# Komorebi_kit.net
KiCad netlist of a schematic drawn in EAGLE
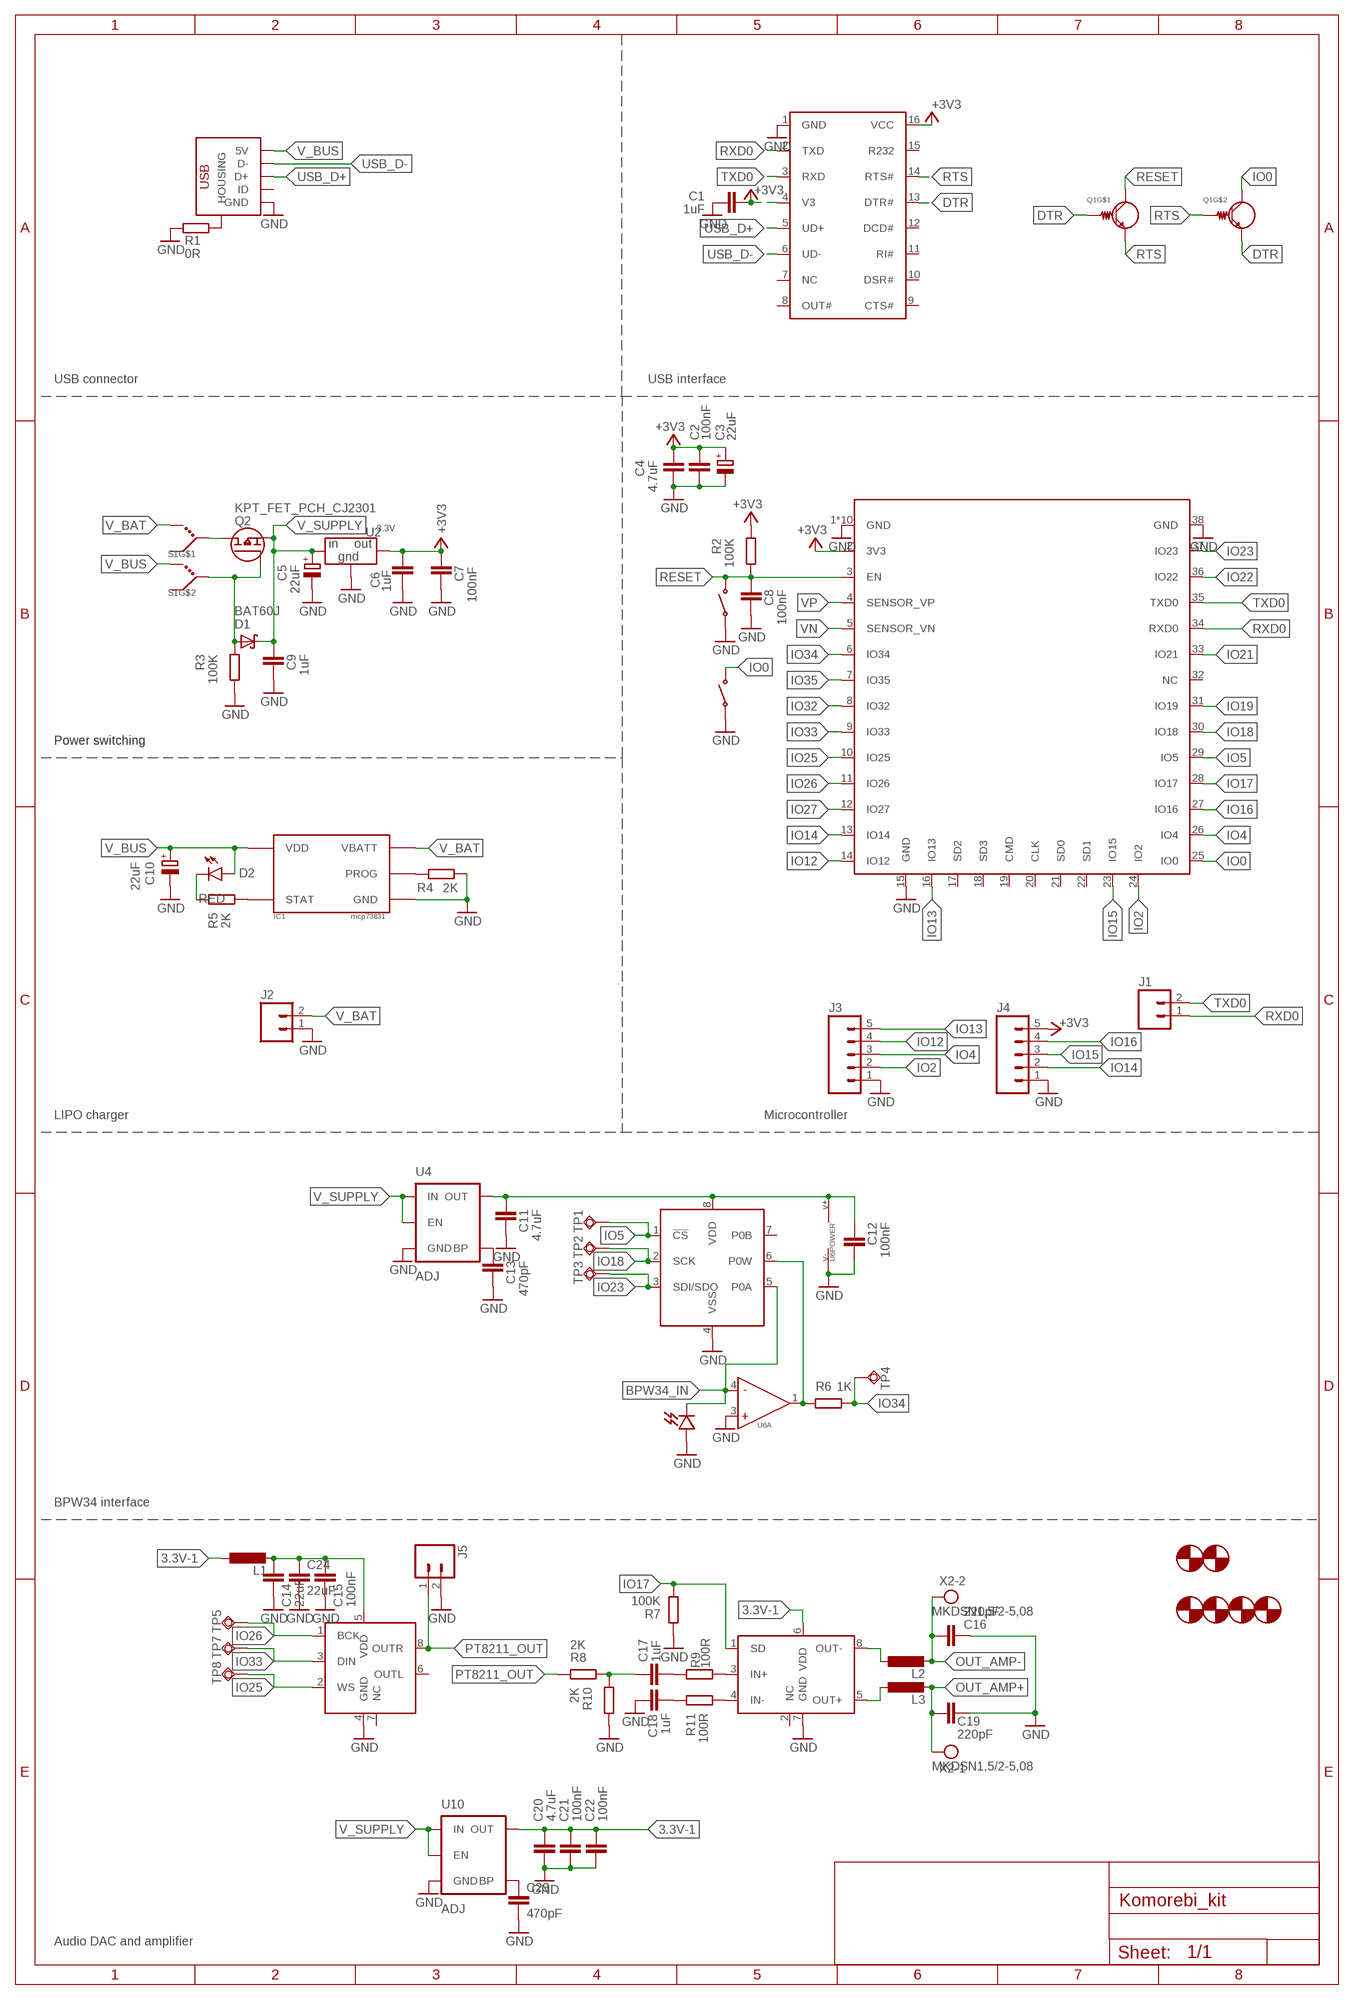
[diagram p0: schematic, sheet 1]

(export (version "E")
  (design (tool "Eeschema 10.0.6"))
  (components
    (comp (ref "C1")
      (value "1uF")
      (footprint "eagle-import:C0603")
      (libsource (lib "eagle-import") (part "C-EUC0603"))
    )
    (comp (ref "C2")
      (value "100nF")
      (footprint "eagle-import:C0603")
      (libsource (lib "eagle-import") (part "C-EUC0603"))
    )
    (comp (ref "C3")
      (value "22uF")
      (footprint "eagle-import:PANASONIC_B")
      (libsource (lib "eagle-import") (part "CPOL-EUB"))
    )
    (comp (ref "C4")
      (value "4.7uF")
      (footprint "eagle-import:C0603")
      (libsource (lib "eagle-import") (part "C-EUC0603"))
    )
    (comp (ref "C5")
      (value "22uF")
      (footprint "eagle-import:PANASONIC_B")
      (libsource (lib "eagle-import") (part "CPOL-EUB"))
    )
    (comp (ref "C6")
      (value "1uF")
      (footprint "eagle-import:C0603")
      (libsource (lib "eagle-import") (part "C-EUC0603"))
    )
    (comp (ref "C7")
      (value "100nF")
      (footprint "eagle-import:C0603")
      (libsource (lib "eagle-import") (part "C-EUC0603"))
    )
    (comp (ref "C8")
      (value "100nF")
      (footprint "eagle-import:C0603")
      (libsource (lib "eagle-import") (part "C-EUC0603"))
    )
    (comp (ref "C9")
      (value "1uF")
      (footprint "eagle-import:C0603")
      (libsource (lib "eagle-import") (part "C-EUC0603"))
    )
    (comp (ref "C10")
      (value "22uF")
      (footprint "eagle-import:PANASONIC_B")
      (libsource (lib "eagle-import") (part "CPOL-EUB"))
    )
    (comp (ref "C11")
      (value "4.7uF")
      (footprint "eagle-import:C0603")
      (libsource (lib "eagle-import") (part "C-EUC0603"))
    )
    (comp (ref "C12")
      (value "100nF")
      (footprint "eagle-import:C0603")
      (libsource (lib "eagle-import") (part "C-EUC0603"))
    )
    (comp (ref "C13")
      (value "470pF")
      (footprint "eagle-import:C0603")
      (libsource (lib "eagle-import") (part "C-EUC0603"))
    )
    (comp (ref "C14")
      (value "22uF")
      (footprint "eagle-import:C0805")
      (libsource (lib "eagle-import") (part "C-EUC0805"))
    )
    (comp (ref "C15")
      (value "100nF")
      (footprint "eagle-import:C0603")
      (libsource (lib "eagle-import") (part "C-EUC0603"))
    )
    (comp (ref "C16")
      (value "220pF")
      (footprint "eagle-import:C0603")
      (libsource (lib "eagle-import") (part "C-EUC0603"))
    )
    (comp (ref "C17")
      (value "1uF")
      (footprint "eagle-import:C0603")
      (libsource (lib "eagle-import") (part "C-EUC0603"))
    )
    (comp (ref "C18")
      (value "1uF")
      (footprint "eagle-import:C0603")
      (libsource (lib "eagle-import") (part "C-EUC0603"))
    )
    (comp (ref "C19")
      (value "220pF")
      (footprint "eagle-import:C0603")
      (libsource (lib "eagle-import") (part "C-EUC0603"))
    )
    (comp (ref "C20")
      (value "4.7uF")
      (footprint "eagle-import:C0603")
      (libsource (lib "eagle-import") (part "C-EUC0603"))
    )
    (comp (ref "C21")
      (value "100nF")
      (footprint "eagle-import:C0603")
      (libsource (lib "eagle-import") (part "C-EUC0603"))
    )
    (comp (ref "C22")
      (value "100nF")
      (footprint "eagle-import:C0603")
      (libsource (lib "eagle-import") (part "C-EUC0603"))
    )
    (comp (ref "C23")
      (value "470pF")
      (footprint "eagle-import:C0603")
      (libsource (lib "eagle-import") (part "C-EUC0603"))
    )
    (comp (ref "C24")
      (value "22uF")
      (footprint "eagle-import:C0805")
      (libsource (lib "eagle-import") (part "C-EUC0805"))
    )
    (comp (ref "D1")
      (value "BAT60J")
      (footprint "eagle-import:SOD323_ST")
      (libsource (lib "eagle-import") (part "BAT60J"))
    )
    (comp (ref "D2")
      (value "RED")
      (footprint "eagle-import:LED-1206")
      (libsource (lib "eagle-import") (part "LED1206"))
    )
    (comp (ref "D3")
      (value "KPT_SENSORS_BPW34")
      (footprint "eagle-import:BPW34")
      (libsource (lib "eagle-import") (part "KPT_SENSORS_BPW34"))
    )
    (comp (ref "H1")
      (value "KPT_HOLE3.0")
      (footprint "eagle-import:3.0MOUNTHOLE")
      (libsource (lib "eagle-import") (part "KPT_HOLE3.0"))
    )
    (comp (ref "H2")
      (value "KPT_HOLE3.0")
      (footprint "eagle-import:3.0MOUNTHOLE")
      (libsource (lib "eagle-import") (part "KPT_HOLE3.0"))
    )
    (comp (ref "H3")
      (value "KPT_HOLE4.1")
      (footprint "eagle-import:4.1MOUNTHOLE")
      (libsource (lib "eagle-import") (part "KPT_HOLE4.1"))
    )
    (comp (ref "H4")
      (value "KPT_HOLE4.1")
      (footprint "eagle-import:4.1MOUNTHOLE")
      (libsource (lib "eagle-import") (part "KPT_HOLE4.1"))
    )
    (comp (ref "H5")
      (value "KPT_HOLE4.1")
      (footprint "eagle-import:4.1MOUNTHOLE")
      (libsource (lib "eagle-import") (part "KPT_HOLE4.1"))
    )
    (comp (ref "H6")
      (value "KPT_HOLE4.1")
      (footprint "eagle-import:4.1MOUNTHOLE")
      (libsource (lib "eagle-import") (part "KPT_HOLE4.1"))
    )
    (comp (ref "IC1")
      (value "KPT_CHARGER_MCP73831")
      (footprint "eagle-import:SOT23-5")
      (libsource (lib "eagle-import") (part "KPT_CHARGER_MCP73831"))
    )
    (comp (ref "J1")
      (value "M02PTH")
      (footprint "eagle-import:1X02")
      (libsource (lib "eagle-import") (part "M02PTH"))
    )
    (comp (ref "J2")
      (value "M02PTH")
      (footprint "eagle-import:1X02")
      (libsource (lib "eagle-import") (part "M02PTH"))
    )
    (comp (ref "J3")
      (value "M05PTH")
      (footprint "eagle-import:1X05")
      (libsource (lib "eagle-import") (part "M05PTH"))
    )
    (comp (ref "J4")
      (value "M05PTH")
      (footprint "eagle-import:1X05")
      (libsource (lib "eagle-import") (part "M05PTH"))
    )
    (comp (ref "J5")
      (value "M02PTH")
      (footprint "eagle-import:1X02")
      (libsource (lib "eagle-import") (part "M02PTH"))
    )
    (comp (ref "L1")
      (value "L-EUL2012C")
      (footprint "eagle-import:L2012C")
      (libsource (lib "eagle-import") (part "L-EUL2012C"))
    )
    (comp (ref "L2")
      (value "L-EUL2012C")
      (footprint "eagle-import:L2012C")
      (libsource (lib "eagle-import") (part "L-EUL2012C"))
    )
    (comp (ref "L3")
      (value "L-EUL2012C")
      (footprint "eagle-import:L2012C")
      (libsource (lib "eagle-import") (part "L-EUL2012C"))
    )
    (comp (ref "Q1")
      (value "KPT_UMH3N")
      (footprint "eagle-import:SOT363")
      (libsource (lib "eagle-import") (part "KPT_UMH3N"))
    )
    (comp (ref "Q2")
      (value "KPT_FET_PCH_CJ2301")
      (footprint "eagle-import:SOT23")
      (libsource (lib "eagle-import") (part "KPT_FET_PCH_CJ2301"))
    )
    (comp (ref "R1")
      (value "0R")
      (footprint "eagle-import:R0603")
      (libsource (lib "eagle-import") (part "R-EU_R0603"))
    )
    (comp (ref "R2")
      (value "100K")
      (footprint "eagle-import:R0603")
      (libsource (lib "eagle-import") (part "R-EU_R0603"))
    )
    (comp (ref "R3")
      (value "100K")
      (footprint "eagle-import:R0603")
      (libsource (lib "eagle-import") (part "R-EU_R0603"))
    )
    (comp (ref "R4")
      (value "2K")
      (footprint "eagle-import:R0603")
      (libsource (lib "eagle-import") (part "R-EU_R0603"))
    )
    (comp (ref "R5")
      (value "2K")
      (footprint "eagle-import:R0603")
      (libsource (lib "eagle-import") (part "R-EU_R0603"))
    )
    (comp (ref "R6")
      (value "1K")
      (footprint "eagle-import:R0603")
      (libsource (lib "eagle-import") (part "R-EU_R0603"))
    )
    (comp (ref "R7")
      (value "100K")
      (footprint "eagle-import:R0603")
      (libsource (lib "eagle-import") (part "R-EU_R0603"))
    )
    (comp (ref "R8")
      (value "2K")
      (footprint "eagle-import:R0603")
      (libsource (lib "eagle-import") (part "R-EU_R0603"))
    )
    (comp (ref "R9")
      (value "100R")
      (footprint "eagle-import:R0603")
      (libsource (lib "eagle-import") (part "R-EU_R0603"))
    )
    (comp (ref "R10")
      (value "2K")
      (footprint "eagle-import:R0603")
      (libsource (lib "eagle-import") (part "R-EU_R0603"))
    )
    (comp (ref "R11")
      (value "100R")
      (footprint "eagle-import:R0603")
      (libsource (lib "eagle-import") (part "R-EU_R0603"))
    )
    (comp (ref "S1")
      (value "KPT_SWITCH_JS202011AQN")
      (footprint "eagle-import:C&K_JS202011AQN")
      (libsource (lib "eagle-import") (part "KPT_SWITCH_JS202011AQN"))
    )
    (comp (ref "S2")
      (value "TACT_SWITCH_C318884")
      (footprint "eagle-import:SWITCH_TACTILE_C318884")
      (libsource (lib "eagle-import") (part "TACT_SWITCH_C318884"))
    )
    (comp (ref "S3")
      (value "TACT_SWITCH_C318884")
      (footprint "eagle-import:SWITCH_TACTILE_C318884")
      (libsource (lib "eagle-import") (part "TACT_SWITCH_C318884"))
    )
    (comp (ref "TP1")
      (value "TPSQB1,27")
      (footprint "eagle-import:B1,27")
      (libsource (lib "eagle-import") (part "TPSQB1,27"))
    )
    (comp (ref "TP2")
      (value "TPSQB1,27")
      (footprint "eagle-import:B1,27")
      (libsource (lib "eagle-import") (part "TPSQB1,27"))
    )
    (comp (ref "TP3")
      (value "TPSQB1,27")
      (footprint "eagle-import:B1,27")
      (libsource (lib "eagle-import") (part "TPSQB1,27"))
    )
    (comp (ref "TP4")
      (value "TPSQB1,27")
      (footprint "eagle-import:B1,27")
      (libsource (lib "eagle-import") (part "TPSQB1,27"))
    )
    (comp (ref "TP5")
      (value "TPSQB1,27")
      (footprint "eagle-import:B1,27")
      (libsource (lib "eagle-import") (part "TPSQB1,27"))
    )
    (comp (ref "TP7")
      (value "TPSQB1,27")
      (footprint "eagle-import:B1,27")
      (libsource (lib "eagle-import") (part "TPSQB1,27"))
    )
    (comp (ref "TP8")
      (value "TPSQB1,27")
      (footprint "eagle-import:B1,27")
      (libsource (lib "eagle-import") (part "TPSQB1,27"))
    )
    (comp (ref "U1")
      (value "KPT_CH340C")
      (footprint "eagle-import:SOIC16")
      (libsource (lib "eagle-import") (part "KPT_CH340C"))
    )
    (comp (ref "U2")
      (value "3.3V")
      (footprint "eagle-import:SOT-89-3L")
      (libsource (lib "eagle-import") (part "KPT_VREG_APT7215"))
    )
    (comp (ref "U3")
      (value "KPT_ESP32")
      (footprint "eagle-import:WROOM_ESP32")
      (libsource (lib "eagle-import") (part "KPT_ESP32"))
    )
    (comp (ref "U4")
      (value "ADJ")
      (footprint "eagle-import:SOT23-5")
      (libsource (lib "eagle-import") (part "V_REG_MIC5205ADJ"))
    )
    (comp (ref "U5")
      (value "KPT_DIGIPOT_MCP41X1SOIC8")
      (footprint "eagle-import:SOIC-8")
      (libsource (lib "eagle-import") (part "KPT_DIGIPOT_MCP41X1SOIC8"))
    )
    (comp (ref "U6")
      (value "KPT_OPAMP_MCP6001")
      (footprint "eagle-import:SOT23-5")
      (libsource (lib "eagle-import") (part "KPT_OPAMP_MCP6001"))
    )
    (comp (ref "U7")
      (value "KPT_DAC_PT8211")
      (footprint "eagle-import:SOIC-8")
      (libsource (lib "eagle-import") (part "KPT_DAC_PT8211"))
    )
    (comp (ref "U8")
      (value "KPT_AMP-D_PAM8302SOIC8")
      (footprint "eagle-import:SOIC-8")
      (libsource (lib "eagle-import") (part "KPT_AMP-D_PAM8302SOIC8"))
    )
    (comp (ref "U10")
      (value "ADJ")
      (footprint "eagle-import:SOT23-5")
      (libsource (lib "eagle-import") (part "V_REG_MIC5205ADJ"))
    )
    (comp (ref "X1")
      (value "USB_MICROB_C10418")
      (footprint "eagle-import:USB_MICROB_C10418")
      (libsource (lib "eagle-import") (part "USB_MICROB_C10418"))
    )
    (comp (ref "X2")
      (value "MKDSN1,5/2-5,08")
      (footprint "eagle-import:MKDSN1,5_2-5,08")
      (libsource (lib "eagle-import") (part "MKDSN1,5/2-5,08"))
    )
  )
  (nets
    (net (code "1") (name "+3V3") (class "Default")
      (node (ref "C1") (pin "2") (pinfunction "2_2") (pintype "passive"))
      (node (ref "C2") (pin "1") (pinfunction "1_1") (pintype "passive"))
      (node (ref "C3") (pin "+") (pinfunction "+_+") (pintype "passive"))
      (node (ref "C4") (pin "2") (pinfunction "2_2") (pintype "passive"))
      (node (ref "C6") (pin "1") (pinfunction "1_1") (pintype "passive"))
      (node (ref "C7") (pin "1") (pinfunction "1_1") (pintype "passive"))
      (node (ref "J4") (pin "5") (pinfunction "5_5") (pintype "passive"))
      (node (ref "R2") (pin "2") (pinfunction "2_2") (pintype "passive"))
      (node (ref "U1") (pin "16") (pinfunction "VCC_16") (pintype "bidirectional"))
      (node (ref "U1") (pin "4") (pinfunction "V3_4") (pintype "bidirectional"))
      (node (ref "U2") (pin "P$3") (pinfunction "OUT_P$3") (pintype "bidirectional"))
      (node (ref "U3") (pin "2") (pinfunction "3V3_2") (pintype "bidirectional"))
    )
    (net (code "2") (name "3.3V-1") (class "Default")
      (node (ref "C20") (pin "1") (pinfunction "1_1") (pintype "passive"))
      (node (ref "C21") (pin "1") (pinfunction "1_1") (pintype "passive"))
      (node (ref "C22") (pin "1") (pinfunction "1_1") (pintype "passive"))
      (node (ref "L1") (pin "1") (pinfunction "1_1") (pintype "passive"))
      (node (ref "U10") (pin "5") (pinfunction "OUT_5") (pintype "passive"))
      (node (ref "U8") (pin "6") (pinfunction "VDD_6") (pintype "bidirectional"))
    )
    (net (code "3") (name "BPW34_IN") (class "Default")
      (node (ref "D3") (pin "CATHODE") (pinfunction "CATHODE_CATHODE") (pintype "bidirectional"))
      (node (ref "U5") (pin "5") (pinfunction "P0A_5") (pintype "bidirectional"))
      (node (ref "U6") (pin "4") (pinfunction "-_4") (pintype "bidirectional"))
    )
    (net (code "4") (name "DTR") (class "Default")
      (node (ref "Q1") (pin "2") (pinfunction "BASE_2") (pintype "bidirectional"))
      (node (ref "Q1") (pin "4") (pinfunction "EMITTER_4") (pintype "bidirectional"))
      (node (ref "U1") (pin "13") (pinfunction "DTR#_13") (pintype "bidirectional"))
    )
    (net (code "5") (name "GND") (class "Default")
      (node (ref "C1") (pin "1") (pinfunction "1_1") (pintype "passive"))
      (node (ref "C10") (pin "-") (pinfunction "-_-") (pintype "passive"))
      (node (ref "C11") (pin "2") (pinfunction "2_2") (pintype "passive"))
      (node (ref "C12") (pin "2") (pinfunction "2_2") (pintype "passive"))
      (node (ref "C13") (pin "2") (pinfunction "2_2") (pintype "passive"))
      (node (ref "C14") (pin "2") (pinfunction "2_2") (pintype "passive"))
      (node (ref "C15") (pin "2") (pinfunction "2_2") (pintype "passive"))
      (node (ref "C16") (pin "1") (pinfunction "1_1") (pintype "passive"))
      (node (ref "C18") (pin "1") (pinfunction "1_1") (pintype "passive"))
      (node (ref "C19") (pin "1") (pinfunction "1_1") (pintype "passive"))
      (node (ref "C2") (pin "2") (pinfunction "2_2") (pintype "passive"))
      (node (ref "C20") (pin "2") (pinfunction "2_2") (pintype "passive"))
      (node (ref "C21") (pin "2") (pinfunction "2_2") (pintype "passive"))
      (node (ref "C22") (pin "2") (pinfunction "2_2") (pintype "passive"))
      (node (ref "C23") (pin "2") (pinfunction "2_2") (pintype "passive"))
      (node (ref "C24") (pin "2") (pinfunction "2_2") (pintype "passive"))
      (node (ref "C3") (pin "-") (pinfunction "-_-") (pintype "passive"))
      (node (ref "C4") (pin "1") (pinfunction "1_1") (pintype "passive"))
      (node (ref "C5") (pin "-") (pinfunction "-_-") (pintype "passive"))
      (node (ref "C6") (pin "2") (pinfunction "2_2") (pintype "passive"))
      (node (ref "C7") (pin "2") (pinfunction "2_2") (pintype "passive"))
      (node (ref "C8") (pin "2") (pinfunction "2_2") (pintype "passive"))
      (node (ref "C9") (pin "2") (pinfunction "2_2") (pintype "passive"))
      (node (ref "D3") (pin "ANODE") (pinfunction "ANODE_ANODE") (pintype "bidirectional"))
      (node (ref "IC1") (pin "2") (pinfunction "GND_2") (pintype "bidirectional"))
      (node (ref "J2") (pin "1") (pinfunction "1_1") (pintype "passive"))
      (node (ref "J3") (pin "1") (pinfunction "1_1") (pintype "passive"))
      (node (ref "J4") (pin "1") (pinfunction "1_1") (pintype "passive"))
      (node (ref "J5") (pin "2") (pinfunction "2_2") (pintype "passive"))
      (node (ref "R1") (pin "1") (pinfunction "1_1") (pintype "passive"))
      (node (ref "R10") (pin "1") (pinfunction "1_1") (pintype "passive"))
      (node (ref "R3") (pin "1") (pinfunction "1_1") (pintype "passive"))
      (node (ref "R4") (pin "2") (pinfunction "2_2") (pintype "passive"))
      (node (ref "R7") (pin "1") (pinfunction "1_1") (pintype "passive"))
      (node (ref "S2") (pin "A") (pinfunction "P$1_A") (pintype "bidirectional"))
      (node (ref "S2") (pin "B") (pinfunction "P$1_B") (pintype "bidirectional"))
      (node (ref "S3") (pin "A") (pinfunction "P$1_A") (pintype "bidirectional"))
      (node (ref "S3") (pin "B") (pinfunction "P$1_B") (pintype "bidirectional"))
      (node (ref "U1") (pin "1") (pinfunction "GND_1") (pintype "bidirectional"))
      (node (ref "U10") (pin "2") (pinfunction "GND_2") (pintype "input"))
      (node (ref "U2") (pin "P$1") (pinfunction "GND_P$1") (pintype "bidirectional"))
      (node (ref "U3") (pin "1") (pinfunction "GND_1") (pintype "bidirectional"))
      (node (ref "U3") (pin "15") (pinfunction "GND_15") (pintype "bidirectional"))
      (node (ref "U3") (pin "38") (pinfunction "GND_38") (pintype "bidirectional"))
      (node (ref "U3") (pin "BP1") (pinfunction "GND_BP1") (pintype "bidirectional"))
      (node (ref "U3") (pin "BP2") (pinfunction "GND_BP2") (pintype "bidirectional"))
      (node (ref "U3") (pin "BP3") (pinfunction "GND_BP3") (pintype "bidirectional"))
      (node (ref "U3") (pin "BP4") (pinfunction "GND_BP4") (pintype "bidirectional"))
      (node (ref "U3") (pin "BP5") (pinfunction "GND_BP5") (pintype "bidirectional"))
      (node (ref "U3") (pin "BP6") (pinfunction "GND_BP6") (pintype "bidirectional"))
      (node (ref "U3") (pin "BP7") (pinfunction "GND_BP7") (pintype "bidirectional"))
      (node (ref "U3") (pin "BP8") (pinfunction "GND_BP8") (pintype "bidirectional"))
      (node (ref "U3") (pin "BP9") (pinfunction "GND_BP9") (pintype "bidirectional"))
      (node (ref "U4") (pin "2") (pinfunction "GND_2") (pintype "input"))
      (node (ref "U5") (pin "4") (pinfunction "VSS_4") (pintype "bidirectional"))
      (node (ref "U6") (pin "2") (pinfunction "V-_2") (pintype "bidirectional"))
      (node (ref "U6") (pin "3") (pinfunction "+_3") (pintype "bidirectional"))
      (node (ref "U7") (pin "4") (pinfunction "GND_4") (pintype "bidirectional"))
      (node (ref "U8") (pin "7") (pinfunction "GND_7") (pintype "bidirectional"))
      (node (ref "X1") (pin "P$1") (pinfunction "GND_P$1") (pintype "bidirectional"))
    )
    (net (code "6") (name "IO0") (class "Default")
      (node (ref "Q1") (pin "3") (pinfunction "COLLECTOR_3") (pintype "bidirectional"))
      (node (ref "S3") (pin "C") (pinfunction "P$2_C") (pintype "bidirectional"))
      (node (ref "S3") (pin "D") (pinfunction "P$2_D") (pintype "bidirectional"))
      (node (ref "U3") (pin "25") (pinfunction "IO0_25") (pintype "bidirectional"))
    )
    (net (code "7") (name "IO2") (class "Default")
      (node (ref "J3") (pin "2") (pinfunction "2_2") (pintype "passive"))
      (node (ref "U3") (pin "24") (pinfunction "IO2_24") (pintype "bidirectional"))
    )
    (net (code "8") (name "IO4") (class "Default")
      (node (ref "J3") (pin "3") (pinfunction "3_3") (pintype "passive"))
      (node (ref "U3") (pin "26") (pinfunction "IO4_26") (pintype "bidirectional"))
    )
    (net (code "9") (name "IO5") (class "Default")
      (node (ref "TP1") (pin "TP") (pinfunction "TP_TP") (pintype "input"))
      (node (ref "U3") (pin "29") (pinfunction "IO5_29") (pintype "bidirectional"))
      (node (ref "U5") (pin "1") (pinfunction "~{CS}_1") (pintype "bidirectional"))
    )
    (net (code "10") (name "IO12") (class "Default")
      (node (ref "J3") (pin "4") (pinfunction "4_4") (pintype "passive"))
      (node (ref "U3") (pin "14") (pinfunction "IO12_14") (pintype "bidirectional"))
    )
    (net (code "11") (name "IO13") (class "Default")
      (node (ref "J3") (pin "5") (pinfunction "5_5") (pintype "passive"))
      (node (ref "U3") (pin "16") (pinfunction "IO13_16") (pintype "bidirectional"))
    )
    (net (code "12") (name "IO14") (class "Default")
      (node (ref "J4") (pin "2") (pinfunction "2_2") (pintype "passive"))
      (node (ref "U3") (pin "13") (pinfunction "IO14_13") (pintype "bidirectional"))
    )
    (net (code "13") (name "IO15") (class "Default")
      (node (ref "J4") (pin "3") (pinfunction "3_3") (pintype "passive"))
      (node (ref "U3") (pin "23") (pinfunction "IO15_23") (pintype "bidirectional"))
    )
    (net (code "14") (name "IO16") (class "Default")
      (node (ref "J4") (pin "4") (pinfunction "4_4") (pintype "passive"))
      (node (ref "U3") (pin "27") (pinfunction "IO16_27") (pintype "bidirectional"))
    )
    (net (code "15") (name "IO17") (class "Default")
      (node (ref "R7") (pin "2") (pinfunction "2_2") (pintype "passive"))
      (node (ref "U3") (pin "28") (pinfunction "IO17_28") (pintype "bidirectional"))
      (node (ref "U8") (pin "1") (pinfunction "SD_1") (pintype "bidirectional"))
    )
    (net (code "16") (name "IO18") (class "Default")
      (node (ref "TP2") (pin "TP") (pinfunction "TP_TP") (pintype "input"))
      (node (ref "U3") (pin "30") (pinfunction "IO18_30") (pintype "bidirectional"))
      (node (ref "U5") (pin "2") (pinfunction "SCK_2") (pintype "bidirectional"))
    )
    (net (code "17") (name "IO19") (class "Default")
      (node (ref "U3") (pin "31") (pinfunction "IO19_31") (pintype "bidirectional"))
    )
    (net (code "18") (name "IO21") (class "Default")
      (node (ref "U3") (pin "33") (pinfunction "IO21_33") (pintype "bidirectional"))
    )
    (net (code "19") (name "IO22") (class "Default")
      (node (ref "U3") (pin "36") (pinfunction "IO22_36") (pintype "bidirectional"))
    )
    (net (code "20") (name "IO23") (class "Default")
      (node (ref "TP3") (pin "TP") (pinfunction "TP_TP") (pintype "input"))
      (node (ref "U3") (pin "37") (pinfunction "IO23_37") (pintype "bidirectional"))
      (node (ref "U5") (pin "3") (pinfunction "SDI/SDO_3") (pintype "bidirectional"))
    )
    (net (code "21") (name "IO25") (class "Default")
      (node (ref "TP8") (pin "TP") (pinfunction "TP_TP") (pintype "input"))
      (node (ref "U3") (pin "10") (pinfunction "IO25_10") (pintype "bidirectional"))
      (node (ref "U7") (pin "2") (pinfunction "WS_2") (pintype "bidirectional"))
    )
    (net (code "22") (name "IO26") (class "Default")
      (node (ref "TP5") (pin "TP") (pinfunction "TP_TP") (pintype "input"))
      (node (ref "U3") (pin "11") (pinfunction "IO26_11") (pintype "bidirectional"))
      (node (ref "U7") (pin "1") (pinfunction "BCK_1") (pintype "bidirectional"))
    )
    (net (code "23") (name "IO27") (class "Default")
      (node (ref "U3") (pin "12") (pinfunction "IO27_12") (pintype "bidirectional"))
    )
    (net (code "24") (name "IO32") (class "Default")
      (node (ref "U3") (pin "8") (pinfunction "IO32_8") (pintype "bidirectional"))
    )
    (net (code "25") (name "IO33") (class "Default")
      (node (ref "TP7") (pin "TP") (pinfunction "TP_TP") (pintype "input"))
      (node (ref "U3") (pin "9") (pinfunction "IO33_9") (pintype "bidirectional"))
      (node (ref "U7") (pin "3") (pinfunction "DIN_3") (pintype "bidirectional"))
    )
    (net (code "26") (name "IO34") (class "Default")
      (node (ref "R6") (pin "1") (pinfunction "1_1") (pintype "passive"))
      (node (ref "TP4") (pin "TP") (pinfunction "TP_TP") (pintype "input"))
      (node (ref "U3") (pin "6") (pinfunction "IO34_6") (pintype "bidirectional"))
    )
    (net (code "27") (name "IO35") (class "Default")
      (node (ref "U3") (pin "7") (pinfunction "IO35_7") (pintype "bidirectional"))
    )
    (net (code "28") (name "Net-(C17-Pad1)") (class "Default")
      (node (ref "C17") (pin "1") (pinfunction "1_1") (pintype "passive"))
      (node (ref "R10") (pin "2") (pinfunction "2_2") (pintype "passive"))
      (node (ref "R8") (pin "2") (pinfunction "2_2") (pintype "passive"))
    )
    (net (code "29") (name "Net-(C17-Pad2)") (class "Default")
      (node (ref "C17") (pin "2") (pinfunction "2_2") (pintype "passive"))
      (node (ref "R9") (pin "1") (pinfunction "1_1") (pintype "passive"))
    )
    (net (code "30") (name "Net-(C18-Pad2)") (class "Default")
      (node (ref "C18") (pin "2") (pinfunction "2_2") (pintype "passive"))
      (node (ref "R11") (pin "1") (pinfunction "1_1") (pintype "passive"))
    )
    (net (code "31") (name "Net-(D2-PadC)") (class "Default")
      (node (ref "D2") (pin "C") (pinfunction "C_C") (pintype "passive"))
      (node (ref "R5") (pin "1") (pinfunction "1_1") (pintype "passive"))
    )
    (net (code "32") (name "Net-(IC1-PROG)") (class "Default")
      (node (ref "IC1") (pin "5") (pinfunction "PROG_5") (pintype "bidirectional"))
      (node (ref "R4") (pin "1") (pinfunction "1_1") (pintype "passive"))
    )
    (net (code "33") (name "Net-(IC1-STAT)") (class "Default")
      (node (ref "IC1") (pin "1") (pinfunction "STAT_1") (pintype "bidirectional"))
      (node (ref "R5") (pin "2") (pinfunction "2_2") (pintype "passive"))
    )
    (net (code "34") (name "Net-(Q2-D)") (class "Default")
      (node (ref "Q2") (pin "3") (pinfunction "D_3") (pintype "bidirectional"))
      (node (ref "S1") (pin "P$2") (pinfunction "COM_P$2") (pintype "bidirectional"))
    )
    (net (code "35") (name "Net-(Q2-G)") (class "Default")
      (node (ref "D1") (pin "A") (pinfunction "A_A") (pintype "passive"))
      (node (ref "Q2") (pin "1") (pinfunction "G_1") (pintype "bidirectional"))
      (node (ref "R3") (pin "2") (pinfunction "2_2") (pintype "passive"))
      (node (ref "S1") (pin "P$5") (pinfunction "COM_P$5") (pintype "bidirectional"))
    )
    (net (code "36") (name "Net-(R1-Pad2)") (class "Default")
      (node (ref "R1") (pin "2") (pinfunction "2_2") (pintype "passive"))
      (node (ref "X1") (pin "P$6") (pinfunction "HOUSING_P$6") (pintype "bidirectional"))
      (node (ref "X1") (pin "P$7") (pinfunction "HOUSING_P$7") (pintype "bidirectional"))
      (node (ref "X1") (pin "P$8") (pinfunction "HOUSING_P$8") (pintype "bidirectional"))
      (node (ref "X1") (pin "P$9") (pinfunction "HOUSING_P$9") (pintype "bidirectional"))
    )
    (net (code "37") (name "Net-(U4-BP)") (class "Default")
      (node (ref "C13") (pin "1") (pinfunction "1_1") (pintype "passive"))
      (node (ref "U4") (pin "4") (pinfunction "BP_4") (pintype "input"))
    )
    (net (code "38") (name "Net-(U4-OUT)") (class "Default")
      (node (ref "C11") (pin "1") (pinfunction "1_1") (pintype "passive"))
      (node (ref "C12") (pin "1") (pinfunction "1_1") (pintype "passive"))
      (node (ref "U4") (pin "5") (pinfunction "OUT_5") (pintype "passive"))
      (node (ref "U5") (pin "8") (pinfunction "VDD_8") (pintype "bidirectional"))
      (node (ref "U6") (pin "5") (pinfunction "V+_5") (pintype "bidirectional"))
    )
    (net (code "39") (name "Net-(U5-P0W)") (class "Default")
      (node (ref "R6") (pin "2") (pinfunction "2_2") (pintype "passive"))
      (node (ref "U5") (pin "6") (pinfunction "P0W_6") (pintype "bidirectional"))
      (node (ref "U6") (pin "1") (pinfunction "OUT_1") (pintype "bidirectional"))
    )
    (net (code "40") (name "Net-(U7-VDD)") (class "Default")
      (node (ref "C14") (pin "1") (pinfunction "1_1") (pintype "passive"))
      (node (ref "C15") (pin "1") (pinfunction "1_1") (pintype "passive"))
      (node (ref "C24") (pin "1") (pinfunction "1_1") (pintype "passive"))
      (node (ref "L1") (pin "2") (pinfunction "2_2") (pintype "passive"))
      (node (ref "U7") (pin "5") (pinfunction "VDD_5") (pintype "bidirectional"))
    )
    (net (code "41") (name "Net-(U8-IN+)") (class "Default")
      (node (ref "R9") (pin "2") (pinfunction "2_2") (pintype "passive"))
      (node (ref "U8") (pin "3") (pinfunction "IN+_3") (pintype "bidirectional"))
    )
    (net (code "42") (name "Net-(U8-IN-)") (class "Default")
      (node (ref "R11") (pin "2") (pinfunction "2_2") (pintype "passive"))
      (node (ref "U8") (pin "4") (pinfunction "IN-_4") (pintype "bidirectional"))
    )
    (net (code "43") (name "Net-(U8-OUT+)") (class "Default")
      (node (ref "L3") (pin "1") (pinfunction "1_1") (pintype "passive"))
      (node (ref "U8") (pin "5") (pinfunction "OUT+_5") (pintype "bidirectional"))
    )
    (net (code "44") (name "Net-(U8-OUT-)") (class "Default")
      (node (ref "L2") (pin "1") (pinfunction "1_1") (pintype "passive"))
      (node (ref "U8") (pin "8") (pinfunction "OUT-_8") (pintype "bidirectional"))
    )
    (net (code "45") (name "Net-(U10-BP)") (class "Default")
      (node (ref "C23") (pin "1") (pinfunction "1_1") (pintype "passive"))
      (node (ref "U10") (pin "4") (pinfunction "BP_4") (pintype "input"))
    )
    (net (code "46") (name "OUT_AMP+") (class "Default")
      (node (ref "C19") (pin "2") (pinfunction "2_2") (pintype "passive"))
      (node (ref "L3") (pin "2") (pinfunction "2_2") (pintype "passive"))
      (node (ref "X2") (pin "1") (pinfunction "KL_1") (pintype "passive"))
    )
    (net (code "47") (name "OUT_AMP-") (class "Default")
      (node (ref "C16") (pin "2") (pinfunction "2_2") (pintype "passive"))
      (node (ref "L2") (pin "2") (pinfunction "2_2") (pintype "passive"))
      (node (ref "X2") (pin "2") (pinfunction "KL_2") (pintype "passive"))
    )
    (net (code "48") (name "PT8211_OUT") (class "Default")
      (node (ref "J5") (pin "1") (pinfunction "1_1") (pintype "passive"))
      (node (ref "R8") (pin "1") (pinfunction "1_1") (pintype "passive"))
      (node (ref "U7") (pin "8") (pinfunction "OUTR_8") (pintype "bidirectional"))
    )
    (net (code "49") (name "RESET") (class "Default")
      (node (ref "C8") (pin "1") (pinfunction "1_1") (pintype "passive"))
      (node (ref "Q1") (pin "6") (pinfunction "COLLECTOR_6") (pintype "bidirectional"))
      (node (ref "R2") (pin "1") (pinfunction "1_1") (pintype "passive"))
      (node (ref "S2") (pin "C") (pinfunction "P$2_C") (pintype "bidirectional"))
      (node (ref "S2") (pin "D") (pinfunction "P$2_D") (pintype "bidirectional"))
      (node (ref "U3") (pin "3") (pinfunction "EN_3") (pintype "bidirectional"))
    )
    (net (code "50") (name "RTS") (class "Default")
      (node (ref "Q1") (pin "1") (pinfunction "EMITTER_1") (pintype "bidirectional"))
      (node (ref "Q1") (pin "5") (pinfunction "BASE_5") (pintype "bidirectional"))
      (node (ref "U1") (pin "14") (pinfunction "RTS#_14") (pintype "bidirectional"))
    )
    (net (code "51") (name "RXD0") (class "Default")
      (node (ref "J1") (pin "1") (pinfunction "1_1") (pintype "passive"))
      (node (ref "U1") (pin "2") (pinfunction "TXD_2") (pintype "bidirectional"))
      (node (ref "U3") (pin "34") (pinfunction "RXD0_34") (pintype "bidirectional"))
    )
    (net (code "52") (name "TXD0") (class "Default")
      (node (ref "J1") (pin "2") (pinfunction "2_2") (pintype "passive"))
      (node (ref "U1") (pin "3") (pinfunction "RXD_3") (pintype "bidirectional"))
      (node (ref "U3") (pin "35") (pinfunction "TXD0_35") (pintype "bidirectional"))
    )
    (net (code "53") (name "USB_D+") (class "Default")
      (node (ref "U1") (pin "5") (pinfunction "UD+_5") (pintype "bidirectional"))
      (node (ref "X1") (pin "P$3") (pinfunction "D+_P$3") (pintype "bidirectional"))
    )
    (net (code "54") (name "USB_D-") (class "Default")
      (node (ref "U1") (pin "6") (pinfunction "UD-_6") (pintype "bidirectional"))
      (node (ref "X1") (pin "P$4") (pinfunction "D-_P$4") (pintype "bidirectional"))
    )
    (net (code "55") (name "VN") (class "Default")
      (node (ref "U3") (pin "5") (pinfunction "SENSOR_VN_5") (pintype "bidirectional"))
    )
    (net (code "56") (name "VP") (class "Default")
      (node (ref "U3") (pin "4") (pinfunction "SENSOR_VP_4") (pintype "bidirectional"))
    )
    (net (code "57") (name "V_BAT") (class "Default")
      (node (ref "IC1") (pin "3") (pinfunction "VBATT_3") (pintype "bidirectional"))
      (node (ref "J2") (pin "2") (pinfunction "2_2") (pintype "passive"))
      (node (ref "S1") (pin "P$3") (pinfunction "SW_ACTION_P$3") (pintype "bidirectional"))
    )
    (net (code "58") (name "V_BUS") (class "Default")
      (node (ref "C10") (pin "+") (pinfunction "+_+") (pintype "passive"))
      (node (ref "D2") (pin "A") (pinfunction "A_A") (pintype "passive"))
      (node (ref "IC1") (pin "4") (pinfunction "VDD_4") (pintype "bidirectional"))
      (node (ref "S1") (pin "P$6") (pinfunction "SW_ACTION_P$6") (pintype "bidirectional"))
      (node (ref "X1") (pin "P$5") (pinfunction "5V_P$5") (pintype "bidirectional"))
    )
    (net (code "59") (name "V_SUPPLY") (class "Default")
      (node (ref "C5") (pin "+") (pinfunction "+_+") (pintype "passive"))
      (node (ref "C9") (pin "1") (pinfunction "1_1") (pintype "passive"))
      (node (ref "D1") (pin "C") (pinfunction "C_C") (pintype "passive"))
      (node (ref "Q2") (pin "2") (pinfunction "S_2") (pintype "bidirectional"))
      (node (ref "U10") (pin "1") (pinfunction "IN_1") (pintype "input"))
      (node (ref "U10") (pin "3") (pinfunction "EN_3") (pintype "input"))
      (node (ref "U2") (pin "P$2") (pinfunction "IN_P$2") (pintype "bidirectional"))
      (node (ref "U2") (pin "P$4") (pinfunction "IN_P$4") (pintype "bidirectional"))
      (node (ref "U4") (pin "1") (pinfunction "IN_1") (pintype "input"))
      (node (ref "U4") (pin "3") (pinfunction "EN_3") (pintype "input"))
    )
    (net (code "60") (name "unconnected-(S1A-SW_REST-PadP$1)") (class "Default")
      (node (ref "S1") (pin "P$1") (pinfunction "SW_REST_P$1") (pintype "bidirectional"))
    )
    (net (code "61") (name "unconnected-(S1B-SW_REST-PadP$4)") (class "Default")
      (node (ref "S1") (pin "P$4") (pinfunction "SW_REST_P$4") (pintype "bidirectional"))
    )
    (net (code "62") (name "unconnected-(U1-CTS#-Pad9)") (class "Default")
      (node (ref "U1") (pin "9") (pinfunction "CTS#_9") (pintype "bidirectional"))
    )
    (net (code "63") (name "unconnected-(U1-DCD#-Pad12)") (class "Default")
      (node (ref "U1") (pin "12") (pinfunction "DCD#_12") (pintype "bidirectional"))
    )
    (net (code "64") (name "unconnected-(U1-DSR#-Pad10)") (class "Default")
      (node (ref "U1") (pin "10") (pinfunction "DSR#_10") (pintype "bidirectional"))
    )
    (net (code "65") (name "unconnected-(U1-NC-Pad7)") (class "Default")
      (node (ref "U1") (pin "7") (pinfunction "NC_7") (pintype "bidirectional"))
    )
    (net (code "66") (name "unconnected-(U1-OUT#-Pad8)") (class "Default")
      (node (ref "U1") (pin "8") (pinfunction "OUT#_8") (pintype "bidirectional"))
    )
    (net (code "67") (name "unconnected-(U1-R232-Pad15)") (class "Default")
      (node (ref "U1") (pin "15") (pinfunction "R232_15") (pintype "bidirectional"))
    )
    (net (code "68") (name "unconnected-(U1-RI#-Pad11)") (class "Default")
      (node (ref "U1") (pin "11") (pinfunction "RI#_11") (pintype "bidirectional"))
    )
    (net (code "69") (name "unconnected-(U3-CLK-Pad20)") (class "Default")
      (node (ref "U3") (pin "20") (pinfunction "CLK_20") (pintype "bidirectional"))
    )
    (net (code "70") (name "unconnected-(U3-CMD-Pad19)") (class "Default")
      (node (ref "U3") (pin "19") (pinfunction "CMD_19") (pintype "bidirectional"))
    )
    (net (code "71") (name "unconnected-(U3-NC-Pad32)") (class "Default")
      (node (ref "U3") (pin "32") (pinfunction "NC_32") (pintype "bidirectional"))
    )
    (net (code "72") (name "unconnected-(U3-SD0-Pad21)") (class "Default")
      (node (ref "U3") (pin "21") (pinfunction "SD0_21") (pintype "bidirectional"))
    )
    (net (code "73") (name "unconnected-(U3-SD1-Pad22)") (class "Default")
      (node (ref "U3") (pin "22") (pinfunction "SD1_22") (pintype "bidirectional"))
    )
    (net (code "74") (name "unconnected-(U3-SD2-Pad17)") (class "Default")
      (node (ref "U3") (pin "17") (pinfunction "SD2_17") (pintype "bidirectional"))
    )
    (net (code "75") (name "unconnected-(U3-SD3-Pad18)") (class "Default")
      (node (ref "U3") (pin "18") (pinfunction "SD3_18") (pintype "bidirectional"))
    )
    (net (code "76") (name "unconnected-(U5-P0B-Pad7)") (class "Default")
      (node (ref "U5") (pin "7") (pinfunction "P0B_7") (pintype "bidirectional"))
    )
    (net (code "77") (name "unconnected-(U7-NC-Pad7)") (class "Default")
      (node (ref "U7") (pin "7") (pinfunction "NC_7") (pintype "bidirectional"))
    )
    (net (code "78") (name "unconnected-(U7-OUTL-Pad6)") (class "Default")
      (node (ref "U7") (pin "6") (pinfunction "OUTL_6") (pintype "bidirectional"))
    )
    (net (code "79") (name "unconnected-(U8-NC-Pad2)") (class "Default")
      (node (ref "U8") (pin "2") (pinfunction "NC_2") (pintype "bidirectional"))
    )
    (net (code "80") (name "unconnected-(X1-ID-PadP$2)") (class "Default")
      (node (ref "X1") (pin "P$2") (pinfunction "ID_P$2") (pintype "bidirectional"))
    )
  )
)
